# 3rd_project.net
KiCad netlist of a schematic drawn in EAGLE
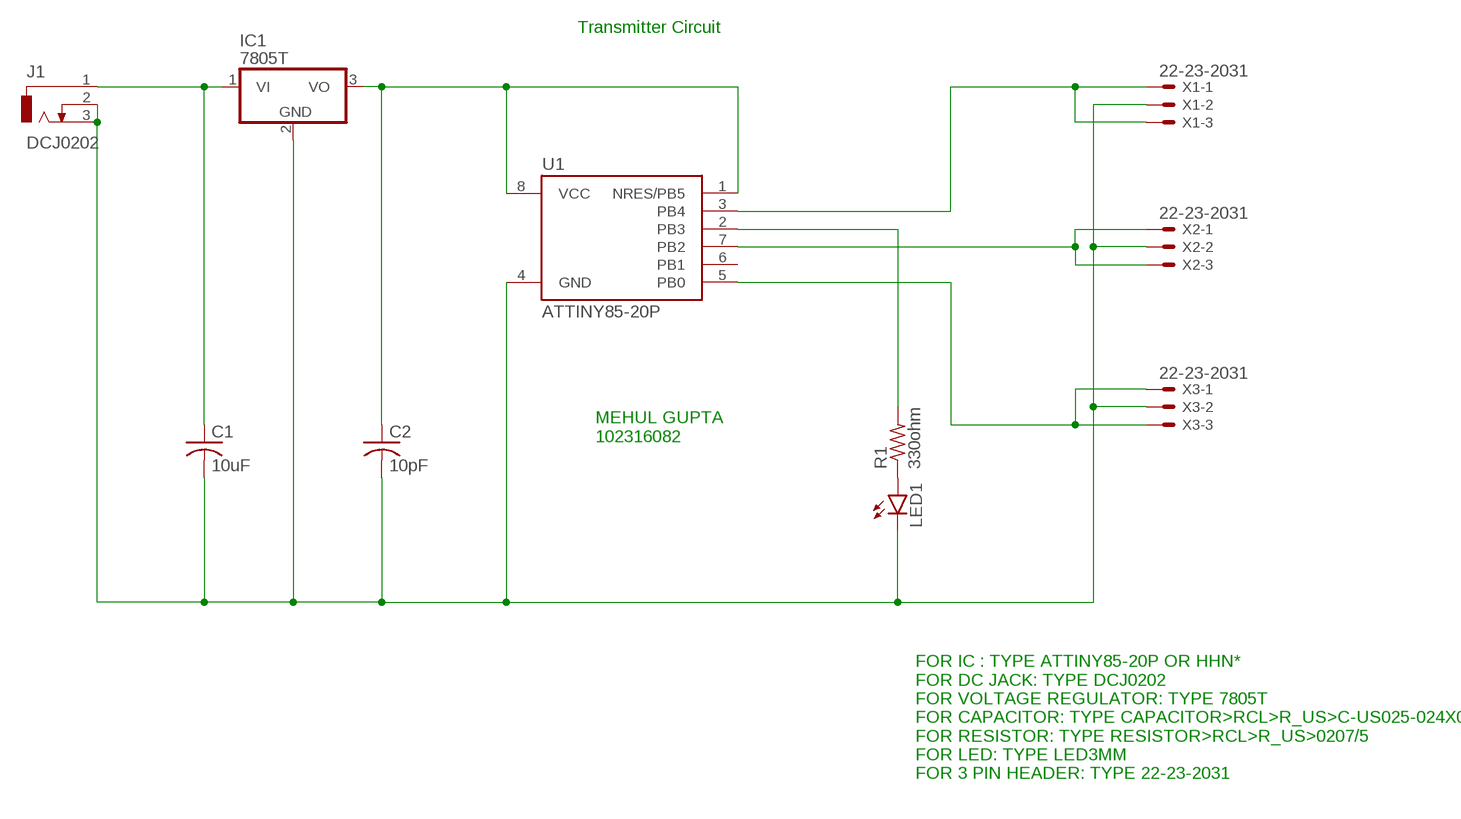
[diagram p0: schematic, sheet 1]

(export (version "E")
  (design (tool "Eeschema 10.0.6"))
  (components
    (comp (ref "C1")
      (value "10uF")
      (footprint "eagle-import:C025-024X044")
      (libsource (lib "eagle-import") (part "C-US025-024X044"))
    )
    (comp (ref "C2")
      (value "10pF")
      (footprint "eagle-import:C025-024X044")
      (libsource (lib "eagle-import") (part "C-US025-024X044"))
    )
    (comp (ref "IC1")
      (value "7805T")
      (footprint "eagle-import:TO220H")
      (libsource (lib "eagle-import") (part "78T05"))
    )
    (comp (ref "J1")
      (value "DCJ0202")
      (footprint "eagle-import:DCJ0202")
      (libsource (lib "eagle-import") (part "DCJ0202"))
    )
    (comp (ref "LED1")
      (value "LED3MM")
      (footprint "eagle-import:LED3MM")
      (libsource (lib "eagle-import") (part "LED3MM"))
    )
    (comp (ref "R1")
      (value "330ohm")
      (footprint "eagle-import:0204_5")
      (libsource (lib "eagle-import") (part "R-US_0204/5"))
    )
    (comp (ref "U1")
      (value "ATTINY85-20P")
      (footprint "eagle-import:PDIP08_300MIL")
      (libsource (lib "eagle-import") (part "ATTINY85P-20"))
    )
    (comp (ref "X1")
      (value "22-23-2031")
      (footprint "eagle-import:22-23-2031")
      (fields (field (name "MF") "MOLEX"))
      (libsource (lib "eagle-import") (part "22-23-2031"))
    )
    (comp (ref "X2")
      (value "22-23-2031")
      (footprint "eagle-import:22-23-2031")
      (fields (field (name "MF") "MOLEX"))
      (libsource (lib "eagle-import") (part "22-23-2031"))
    )
    (comp (ref "X3")
      (value "22-23-2031")
      (footprint "eagle-import:22-23-2031")
      (fields (field (name "MF") "MOLEX"))
      (libsource (lib "eagle-import") (part "22-23-2031"))
    )
  )
  (nets
    (net (code "1") (name "Net-(IC1-GND)") (class "Default")
      (node (ref "C1") (pin "2") (pinfunction "2_2") (pintype "passive"))
      (node (ref "C2") (pin "2") (pinfunction "2_2") (pintype "passive"))
      (node (ref "IC1") (pin "2") (pinfunction "GND_2") (pintype "passive"))
      (node (ref "J1") (pin "2") (pinfunction "2_2") (pintype "passive"))
      (node (ref "J1") (pin "3") (pinfunction "3_3") (pintype "passive"))
      (node (ref "LED1") (pin "K") (pinfunction "C_K") (pintype "passive"))
      (node (ref "U1") (pin "4") (pinfunction "GND_4") (pintype "power_in"))
      (node (ref "X1") (pin "2") (pinfunction "S_2") (pintype "passive"))
      (node (ref "X2") (pin "2") (pinfunction "S_2") (pintype "passive"))
      (node (ref "X3") (pin "2") (pinfunction "S_2") (pintype "passive"))
    )
    (net (code "2") (name "Net-(IC1-VI)") (class "Default")
      (node (ref "C1") (pin "1") (pinfunction "1_1") (pintype "passive"))
      (node (ref "IC1") (pin "1") (pinfunction "VI_1") (pintype "input"))
      (node (ref "J1") (pin "1") (pinfunction "1_1") (pintype "passive"))
    )
    (net (code "3") (name "Net-(IC1-VO)") (class "Default")
      (node (ref "C2") (pin "1") (pinfunction "1_1") (pintype "passive"))
      (node (ref "IC1") (pin "3") (pinfunction "VO_3") (pintype "passive"))
      (node (ref "U1") (pin "1") (pinfunction "NRES/PB5_1") (pintype "bidirectional"))
      (node (ref "U1") (pin "8") (pinfunction "VCC_8") (pintype "power_in"))
    )
    (net (code "4") (name "Net-(LED1-PadA)") (class "Default")
      (node (ref "LED1") (pin "A") (pinfunction "A_A") (pintype "passive"))
      (node (ref "R1") (pin "1") (pinfunction "1_1") (pintype "passive"))
    )
    (net (code "5") (name "Net-(U1-PB0)") (class "Default")
      (node (ref "U1") (pin "5") (pinfunction "PB0_5") (pintype "bidirectional"))
      (node (ref "X3") (pin "1") (pinfunction "S_1") (pintype "passive"))
      (node (ref "X3") (pin "3") (pinfunction "S_3") (pintype "passive"))
    )
    (net (code "6") (name "Net-(U1-PB2)") (class "Default")
      (node (ref "U1") (pin "7") (pinfunction "PB2_7") (pintype "bidirectional"))
      (node (ref "X2") (pin "1") (pinfunction "S_1") (pintype "passive"))
      (node (ref "X2") (pin "3") (pinfunction "S_3") (pintype "passive"))
    )
    (net (code "7") (name "Net-(U1-PB3)") (class "Default")
      (node (ref "R1") (pin "2") (pinfunction "2_2") (pintype "passive"))
      (node (ref "U1") (pin "2") (pinfunction "PB3_2") (pintype "bidirectional"))
    )
    (net (code "8") (name "Net-(U1-PB4)") (class "Default")
      (node (ref "U1") (pin "3") (pinfunction "PB4_3") (pintype "bidirectional"))
      (node (ref "X1") (pin "1") (pinfunction "S_1") (pintype "passive"))
      (node (ref "X1") (pin "3") (pinfunction "S_3") (pintype "passive"))
    )
    (net (code "9") (name "unconnected-(U1-PB1-Pad6)") (class "Default")
      (node (ref "U1") (pin "6") (pinfunction "PB1_6") (pintype "bidirectional"))
    )
  )
)
